# Microcontroller.net
KiCad netlist of a schematic drawn in Altium Designer
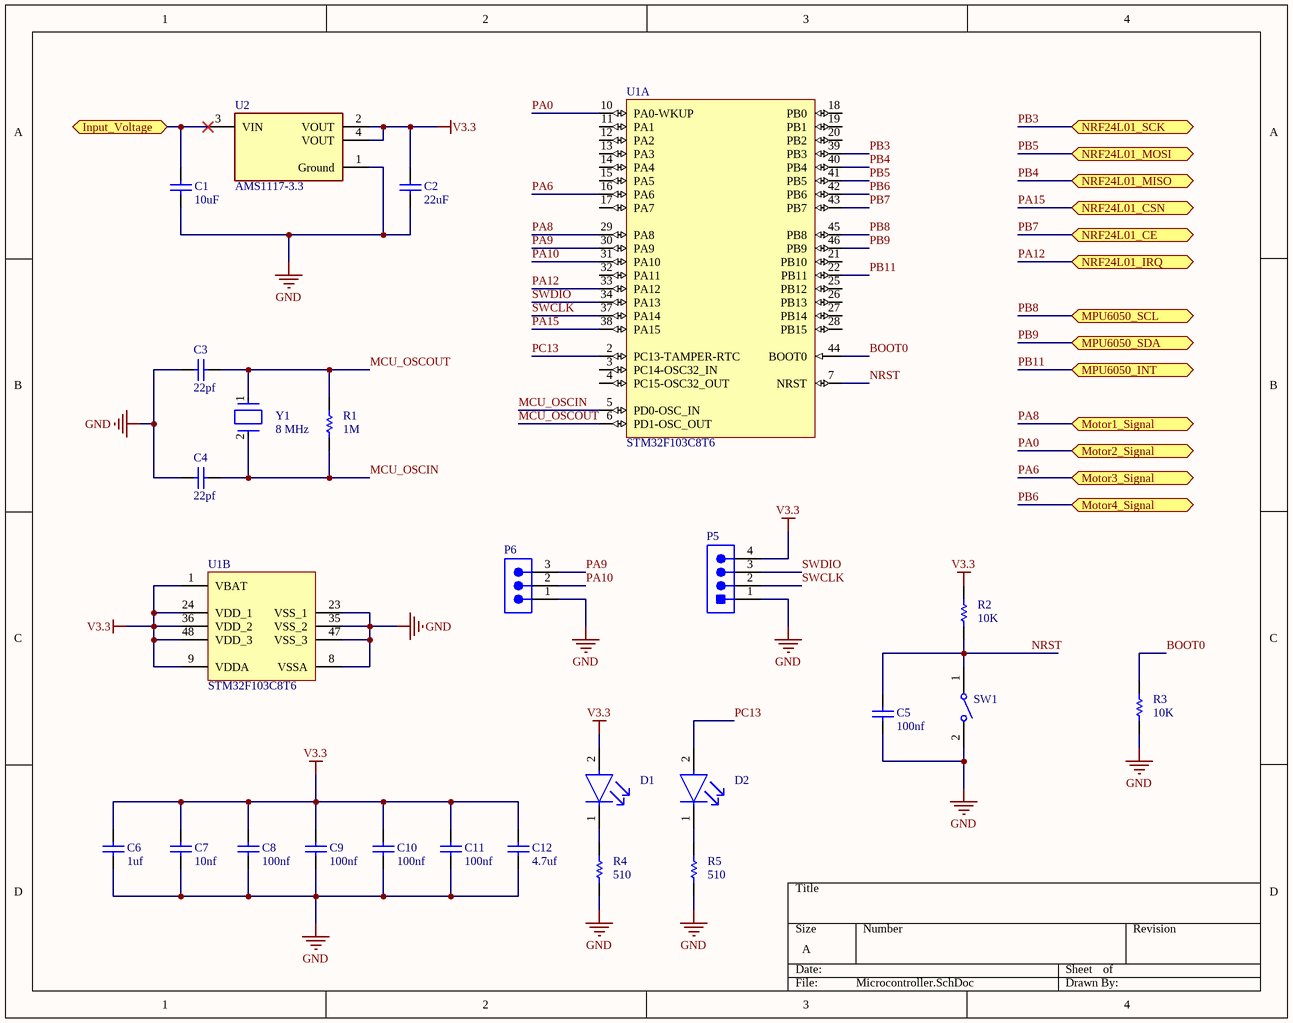
[diagram p0: Microcontroller.SchDoc]

(export (version "E")
  (design (tool "Eeschema 10.0.6"))
  (components
    (comp (ref "C1")
      (value "10uF")
      (footprint "CAPC1206(3216)190_N")
      (description "CAP 1206")
      (fields (field (name "TOLERANCE") "Â±10%"))
      (libsource (lib "Altium Content Vault") (part "CAP"))
    )
    (comp (ref "C2")
      (value "22uF")
      (footprint "CAPC1206(3216)190_N")
      (description "CAP 1206")
      (fields (field (name "TOLERANCE") "Â±10%"))
      (libsource (lib "Altium Content Vault") (part "CAP"))
    )
    (comp (ref "C3")
      (value "22pf")
      (footprint "CAPC1206(3216)190_N")
      (description "CAP 1206")
      (fields (field (name "TOLERANCE") "Â±10%"))
      (libsource (lib "Altium Content Vault") (part "CAP"))
    )
    (comp (ref "C4")
      (value "22pf")
      (footprint "CAPC1206(3216)190_N")
      (description "CAP 1206")
      (fields (field (name "TOLERANCE") "Â±10%"))
      (libsource (lib "Altium Content Vault") (part "CAP"))
    )
    (comp (ref "C5")
      (value "100nf")
      (footprint "CAPC1206(3216)190_N")
      (description "CAP 1206")
      (fields (field (name "TOLERANCE") "Â±10%"))
      (libsource (lib "Altium Content Vault") (part "CAP"))
    )
    (comp (ref "C6")
      (value "1uf")
      (footprint "CAPC1206(3216)190_N")
      (description "CAP 1206")
      (fields (field (name "TOLERANCE") "Â±10%"))
      (libsource (lib "Altium Content Vault") (part "CAP"))
    )
    (comp (ref "C7")
      (value "10nf")
      (footprint "CAPC1206(3216)190_N")
      (description "CAP 1206")
      (fields (field (name "TOLERANCE") "Â±10%"))
      (libsource (lib "Altium Content Vault") (part "CAP"))
    )
    (comp (ref "C8")
      (value "100nf")
      (footprint "CAPC1206(3216)190_N")
      (description "CAP 1206")
      (fields (field (name "TOLERANCE") "Â±10%"))
      (libsource (lib "Altium Content Vault") (part "CAP"))
    )
    (comp (ref "C9")
      (value "100nf")
      (footprint "CAPC1206(3216)190_N")
      (description "CAP 1206")
      (fields (field (name "TOLERANCE") "Â±10%"))
      (libsource (lib "Altium Content Vault") (part "CAP"))
    )
    (comp (ref "C10")
      (value "100nf")
      (footprint "CAPC1206(3216)190_N")
      (description "CAP 1206")
      (fields (field (name "TOLERANCE") "Â±10%"))
      (libsource (lib "Altium Content Vault") (part "CAP"))
    )
    (comp (ref "C11")
      (value "100nf")
      (footprint "CAPC1206(3216)190_N")
      (description "CAP 1206")
      (fields (field (name "TOLERANCE") "Â±10%"))
      (libsource (lib "Altium Content Vault") (part "CAP"))
    )
    (comp (ref "C12")
      (value "4.7uf")
      (footprint "CAPC1206(3216)190_N")
      (description "CAP 1206")
      (fields (field (name "TOLERANCE") "Â±10%"))
      (libsource (lib "Altium Content Vault") (part "CAP"))
    )
    (comp (ref "D1")
      (value "Power")
      (footprint "FP-CMD15-21-MFG")
      (description "LED RED DIFFUSED 1206 SMD")
      (fields (field (name "MANUFACTURER") "VCC") (field (name "MANUFACTURER PART NUMBER") "CMD15-21VRD/TR8"))
      (libsource (lib "Altium Content Vault") (part "8706943c75ba83719d021d2fdc84c58"))
    )
    (comp (ref "D2")
      (value "Status")
      (footprint "FP-CMD15-21-MFG")
      (description "LED RED DIFFUSED 1206 SMD")
      (fields (field (name "MANUFACTURER") "VCC") (field (name "MANUFACTURER PART NUMBER") "CMD15-21VRD/TR8"))
      (libsource (lib "Altium Content Vault") (part "8706943c75ba83719d021d2fdc84c58"))
    )
    (comp (ref "P5")
      (value "Program Port")
      (footprint "TECO-280371-2_V")
      (fields (field (name "MANUFACTURER") "TE Connectivity"))
      (libsource (lib "Altium Content Vault") (part "CN-1P-M-R4"))
    )
    (comp (ref "P6")
      (value "Serial Port")
      (footprint "61900311121")
      (libsource (lib "Altium Content Vault") (part "Header_Male_1R_03P"))
    )
    (comp (ref "R1")
      (value "1M")
      (footprint "RESC3216X70X50NL05T20")
      (fields (field (name "MANUFACTURER") "Panasonic") (field (name "PART NUMBER") "ERJ-8GEY0R00V"))
      (libsource (lib "Altium Content Vault") (part "RES"))
    )
    (comp (ref "R2")
      (value "10K")
      (footprint "RESC3216X70X50NL05T20")
      (fields (field (name "MANUFACTURER") "Panasonic") (field (name "PART NUMBER") "ERJ-8GEY0R00V"))
      (libsource (lib "Altium Content Vault") (part "RES"))
    )
    (comp (ref "R3")
      (value "10K")
      (footprint "RESC3216X70X50NL05T20")
      (fields (field (name "MANUFACTURER") "Panasonic") (field (name "PART NUMBER") "ERJ-8GEY0R00V"))
      (libsource (lib "Altium Content Vault") (part "RES"))
    )
    (comp (ref "R4")
      (value "510")
      (footprint "RESC3216X70X50NL05T20")
      (fields (field (name "MANUFACTURER") "Panasonic") (field (name "PART NUMBER") "ERJ-8GEY0R00V"))
      (libsource (lib "Altium Content Vault") (part "RES"))
    )
    (comp (ref "R5")
      (value "510")
      (footprint "RESC3216X70X50NL05T20")
      (fields (field (name "MANUFACTURER") "Panasonic") (field (name "PART NUMBER") "ERJ-8GEY0R00V"))
      (libsource (lib "Altium Content Vault") (part "RES"))
    )
    (comp (ref "SW1")
      (value "FSMSM")
      (footprint "TECO-FSMSM-2_V")
      (description "FSMSM Push Button Switch, 50 mA, -35 to 85 degC, 2-Pin SMD, RoHS, Bulk")
      (fields (field (name "MANUFACTURER") "TE Connectivity"))
      (libsource (lib "Altium Content Vault") (part "SW-SPST-2_C"))
    )
    (comp (ref "U1")
      (value "STM32F103C8T6")
      (footprint "STM-LQFP48_L")
      (libsource (lib "Altium Content Vault") (part "MC-ARM-STM32F103X8_B-SQ48"))
    )
    (comp (ref "U2")
      (value "AMS1117-3.3")
      (footprint "FP-AMS1117-IPC_C")
      (description "LDO Voltage Regulators 1A, 3.3V")
      (fields
        (field (name "OCTOPART") "https://octopart.com/ams1117-3.3-advanced+monolithic+systems-25899300")
        (field (name "MANUFACTURER") "Advanced Monolithic Systems")
      )
      (libsource (lib "Altium Content Vault") (part "8bdbb5f8e77002000e30dd2845d0354"))
    )
    (comp (ref "Y1")
      (value "ABLS-8.000MHZ-B2-T")
      (footprint "FP-ABLS-MFG")
      (description "CRYSTAL 8.0000MHZ 18PF SMD")
      (fields (field (name "OPERATING FREQUENCY") "8 MHz") (field (name "TOLERANCE") "20ppm"))
      (libsource (lib "Altium Content Vault") (part "c23a69dc6c9e2f18f2079038eb95dd1"))
    )
  )
  (nets
    (net (code "1") (name "/BOOT0") (class "Default")
      (node (ref "R3") (pin "2") (pinfunction "2_2") (pintype "passive"))
      (node (ref "U1") (pin "44") (pinfunction "BOOT0_44") (pintype "input"))
    )
    (net (code "2") (name "/Input_Voltage") (class "Default")
      (node (ref "C1") (pin "2") (pinfunction "2_2") (pintype "passive"))
      (node (ref "U2") (pin "3") (pinfunction "VIN_3") (pintype "power_in"))
    )
    (net (code "3") (name "/MCU_OSCIN") (class "Default")
      (node (ref "C4") (pin "1") (pinfunction "1_1") (pintype "passive"))
      (node (ref "R1") (pin "1") (pinfunction "1_1") (pintype "passive"))
      (node (ref "U1") (pin "5") (pinfunction "PD0-OSC_IN_5") (pintype "bidirectional"))
      (node (ref "Y1") (pin "2") (pinfunction "2_2") (pintype "passive"))
    )
    (net (code "4") (name "/MCU_OSCOUT") (class "Default")
      (node (ref "C3") (pin "1") (pinfunction "1_1") (pintype "passive"))
      (node (ref "R1") (pin "2") (pinfunction "2_2") (pintype "passive"))
      (node (ref "U1") (pin "6") (pinfunction "PD1-OSC_OUT_6") (pintype "bidirectional"))
      (node (ref "Y1") (pin "1") (pinfunction "1_1") (pintype "passive"))
    )
    (net (code "5") (name "/NRST") (class "Default")
      (node (ref "C5") (pin "2") (pinfunction "2_2") (pintype "passive"))
      (node (ref "R2") (pin "1") (pinfunction "1_1") (pintype "passive"))
      (node (ref "SW1") (pin "1") (pinfunction "1_1") (pintype "passive"))
      (node (ref "U1") (pin "7") (pinfunction "NRST_7") (pintype "bidirectional"))
    )
    (net (code "6") (name "/PA0") (class "Default")
      (node (ref "U1") (pin "10") (pinfunction "PA0-WKUP_10") (pintype "bidirectional"))
    )
    (net (code "7") (name "/PA6") (class "Default")
      (node (ref "U1") (pin "16") (pinfunction "PA6_16") (pintype "bidirectional"))
    )
    (net (code "8") (name "/PA8") (class "Default")
      (node (ref "U1") (pin "29") (pinfunction "PA8_29") (pintype "bidirectional"))
    )
    (net (code "9") (name "/PA9") (class "Default")
      (node (ref "P6") (pin "3") (pinfunction "3_3") (pintype "passive"))
      (node (ref "U1") (pin "30") (pinfunction "PA9_30") (pintype "bidirectional"))
    )
    (net (code "10") (name "/PA10") (class "Default")
      (node (ref "P6") (pin "2") (pinfunction "2_2") (pintype "passive"))
      (node (ref "U1") (pin "31") (pinfunction "PA10_31") (pintype "bidirectional"))
    )
    (net (code "11") (name "/PA12") (class "Default")
      (node (ref "U1") (pin "33") (pinfunction "PA12_33") (pintype "bidirectional"))
    )
    (net (code "12") (name "/PA15") (class "Default")
      (node (ref "U1") (pin "38") (pinfunction "PA15_38") (pintype "bidirectional"))
    )
    (net (code "13") (name "/PB3") (class "Default")
      (node (ref "U1") (pin "39") (pinfunction "PB3_39") (pintype "bidirectional"))
    )
    (net (code "14") (name "/PB4") (class "Default")
      (node (ref "U1") (pin "40") (pinfunction "PB4_40") (pintype "bidirectional"))
    )
    (net (code "15") (name "/PB5") (class "Default")
      (node (ref "U1") (pin "41") (pinfunction "PB5_41") (pintype "bidirectional"))
    )
    (net (code "16") (name "/PB6") (class "Default")
      (node (ref "U1") (pin "42") (pinfunction "PB6_42") (pintype "bidirectional"))
    )
    (net (code "17") (name "/PB7") (class "Default")
      (node (ref "U1") (pin "43") (pinfunction "PB7_43") (pintype "bidirectional"))
    )
    (net (code "18") (name "/PB8") (class "Default")
      (node (ref "U1") (pin "45") (pinfunction "PB8_45") (pintype "bidirectional"))
    )
    (net (code "19") (name "/PB9") (class "Default")
      (node (ref "U1") (pin "46") (pinfunction "PB9_46") (pintype "bidirectional"))
    )
    (net (code "20") (name "/PB11") (class "Default")
      (node (ref "U1") (pin "22") (pinfunction "PB11_22") (pintype "bidirectional"))
    )
    (net (code "21") (name "/PC13") (class "Default")
      (node (ref "D2") (pin "2") (pinfunction "A_2") (pintype "passive"))
      (node (ref "U1") (pin "2") (pinfunction "PC13-TAMPER-RTC_2") (pintype "bidirectional"))
    )
    (net (code "22") (name "/SWCLK") (class "Default")
      (node (ref "P5") (pin "2") (pinfunction "2_2") (pintype "passive"))
      (node (ref "U1") (pin "37") (pinfunction "PA14_37") (pintype "bidirectional"))
    )
    (net (code "23") (name "/SWDIO") (class "Default")
      (node (ref "P5") (pin "3") (pinfunction "3_3") (pintype "passive"))
      (node (ref "U1") (pin "34") (pinfunction "PA13_34") (pintype "bidirectional"))
    )
    (net (code "24") (name "GND") (class "Default")
      (node (ref "C1") (pin "1") (pinfunction "1_1") (pintype "passive"))
      (node (ref "C10") (pin "1") (pinfunction "1_1") (pintype "passive"))
      (node (ref "C11") (pin "1") (pinfunction "1_1") (pintype "passive"))
      (node (ref "C12") (pin "1") (pinfunction "1_1") (pintype "passive"))
      (node (ref "C2") (pin "1") (pinfunction "1_1") (pintype "passive"))
      (node (ref "C3") (pin "2") (pinfunction "2_2") (pintype "passive"))
      (node (ref "C4") (pin "2") (pinfunction "2_2") (pintype "passive"))
      (node (ref "C5") (pin "1") (pinfunction "1_1") (pintype "passive"))
      (node (ref "C6") (pin "1") (pinfunction "1_1") (pintype "passive"))
      (node (ref "C7") (pin "1") (pinfunction "1_1") (pintype "passive"))
      (node (ref "C8") (pin "1") (pinfunction "1_1") (pintype "passive"))
      (node (ref "C9") (pin "1") (pinfunction "1_1") (pintype "passive"))
      (node (ref "P5") (pin "1") (pinfunction "1_1") (pintype "passive"))
      (node (ref "P6") (pin "1") (pinfunction "1_1") (pintype "passive"))
      (node (ref "R3") (pin "1") (pinfunction "1_1") (pintype "passive"))
      (node (ref "R4") (pin "1") (pinfunction "1_1") (pintype "passive"))
      (node (ref "R5") (pin "1") (pinfunction "1_1") (pintype "passive"))
      (node (ref "SW1") (pin "2") (pinfunction "2_2") (pintype "passive"))
      (node (ref "U1") (pin "23") (pinfunction "VSS_1_23") (pintype "power_in"))
      (node (ref "U1") (pin "35") (pinfunction "VSS_2_35") (pintype "power_in"))
      (node (ref "U1") (pin "47") (pinfunction "VSS_3_47") (pintype "power_in"))
      (node (ref "U1") (pin "8") (pinfunction "VSSA_8") (pintype "power_in"))
      (node (ref "U2") (pin "1") (pinfunction "Ground_1") (pintype "power_in"))
    )
    (net (code "25") (name "Net-(D1-C)") (class "Default")
      (node (ref "D1") (pin "1") (pinfunction "C_1") (pintype "passive"))
      (node (ref "R4") (pin "2") (pinfunction "2_2") (pintype "passive"))
    )
    (net (code "26") (name "Net-(D2-C)") (class "Default")
      (node (ref "D2") (pin "1") (pinfunction "C_1") (pintype "passive"))
      (node (ref "R5") (pin "2") (pinfunction "2_2") (pintype "passive"))
    )
    (net (code "27") (name "V3.3") (class "Default")
      (node (ref "C10") (pin "2") (pinfunction "2_2") (pintype "passive"))
      (node (ref "C11") (pin "2") (pinfunction "2_2") (pintype "passive"))
      (node (ref "C12") (pin "2") (pinfunction "2_2") (pintype "passive"))
      (node (ref "C2") (pin "2") (pinfunction "2_2") (pintype "passive"))
      (node (ref "C6") (pin "2") (pinfunction "2_2") (pintype "passive"))
      (node (ref "C7") (pin "2") (pinfunction "2_2") (pintype "passive"))
      (node (ref "C8") (pin "2") (pinfunction "2_2") (pintype "passive"))
      (node (ref "C9") (pin "2") (pinfunction "2_2") (pintype "passive"))
      (node (ref "D1") (pin "2") (pinfunction "A_2") (pintype "passive"))
      (node (ref "P5") (pin "4") (pinfunction "4_4") (pintype "passive"))
      (node (ref "R2") (pin "2") (pinfunction "2_2") (pintype "passive"))
      (node (ref "U1") (pin "1") (pinfunction "VBAT_1") (pintype "power_in"))
      (node (ref "U1") (pin "24") (pinfunction "VDD_1_24") (pintype "power_in"))
      (node (ref "U1") (pin "36") (pinfunction "VDD_2_36") (pintype "power_in"))
      (node (ref "U1") (pin "48") (pinfunction "VDD_3_48") (pintype "power_in"))
      (node (ref "U1") (pin "9") (pinfunction "VDDA_9") (pintype "power_in"))
      (node (ref "U2") (pin "2") (pinfunction "VOUT_2") (pintype "passive"))
      (node (ref "U2") (pin "4") (pinfunction "VOUT_4") (pintype "passive"))
    )
    (net (code "28") (name "unconnected-(U1A-PA1-Pad11)") (class "Default")
      (node (ref "U1") (pin "11") (pinfunction "PA1_11") (pintype "bidirectional"))
    )
    (net (code "29") (name "unconnected-(U1A-PA2-Pad12)") (class "Default")
      (node (ref "U1") (pin "12") (pinfunction "PA2_12") (pintype "bidirectional"))
    )
    (net (code "30") (name "unconnected-(U1A-PA3-Pad13)") (class "Default")
      (node (ref "U1") (pin "13") (pinfunction "PA3_13") (pintype "bidirectional"))
    )
    (net (code "31") (name "unconnected-(U1A-PA4-Pad14)") (class "Default")
      (node (ref "U1") (pin "14") (pinfunction "PA4_14") (pintype "bidirectional"))
    )
    (net (code "32") (name "unconnected-(U1A-PA5-Pad15)") (class "Default")
      (node (ref "U1") (pin "15") (pinfunction "PA5_15") (pintype "bidirectional"))
    )
    (net (code "33") (name "unconnected-(U1A-PA7-Pad17)") (class "Default")
      (node (ref "U1") (pin "17") (pinfunction "PA7_17") (pintype "bidirectional"))
    )
    (net (code "34") (name "unconnected-(U1A-PA11-Pad32)") (class "Default")
      (node (ref "U1") (pin "32") (pinfunction "PA11_32") (pintype "bidirectional"))
    )
    (net (code "35") (name "unconnected-(U1A-PB0-Pad18)") (class "Default")
      (node (ref "U1") (pin "18") (pinfunction "PB0_18") (pintype "bidirectional"))
    )
    (net (code "36") (name "unconnected-(U1A-PB1-Pad19)") (class "Default")
      (node (ref "U1") (pin "19") (pinfunction "PB1_19") (pintype "bidirectional"))
    )
    (net (code "37") (name "unconnected-(U1A-PB2-Pad20)") (class "Default")
      (node (ref "U1") (pin "20") (pinfunction "PB2_20") (pintype "bidirectional"))
    )
    (net (code "38") (name "unconnected-(U1A-PB10-Pad21)") (class "Default")
      (node (ref "U1") (pin "21") (pinfunction "PB10_21") (pintype "bidirectional"))
    )
    (net (code "39") (name "unconnected-(U1A-PB12-Pad25)") (class "Default")
      (node (ref "U1") (pin "25") (pinfunction "PB12_25") (pintype "bidirectional"))
    )
    (net (code "40") (name "unconnected-(U1A-PB13-Pad26)") (class "Default")
      (node (ref "U1") (pin "26") (pinfunction "PB13_26") (pintype "bidirectional"))
    )
    (net (code "41") (name "unconnected-(U1A-PB14-Pad27)") (class "Default")
      (node (ref "U1") (pin "27") (pinfunction "PB14_27") (pintype "bidirectional"))
    )
    (net (code "42") (name "unconnected-(U1A-PB15-Pad28)") (class "Default")
      (node (ref "U1") (pin "28") (pinfunction "PB15_28") (pintype "bidirectional"))
    )
    (net (code "43") (name "unconnected-(U1A-PC14-OSC32_IN-Pad3)") (class "Default")
      (node (ref "U1") (pin "3") (pinfunction "PC14-OSC32_IN_3") (pintype "bidirectional"))
    )
    (net (code "44") (name "unconnected-(U1A-PC15-OSC32_OUT-Pad4)") (class "Default")
      (node (ref "U1") (pin "4") (pinfunction "PC15-OSC32_OUT_4") (pintype "bidirectional"))
    )
  )
)
